# sheet.net
KiCad netlist of a schematic drawn in Altium Designer
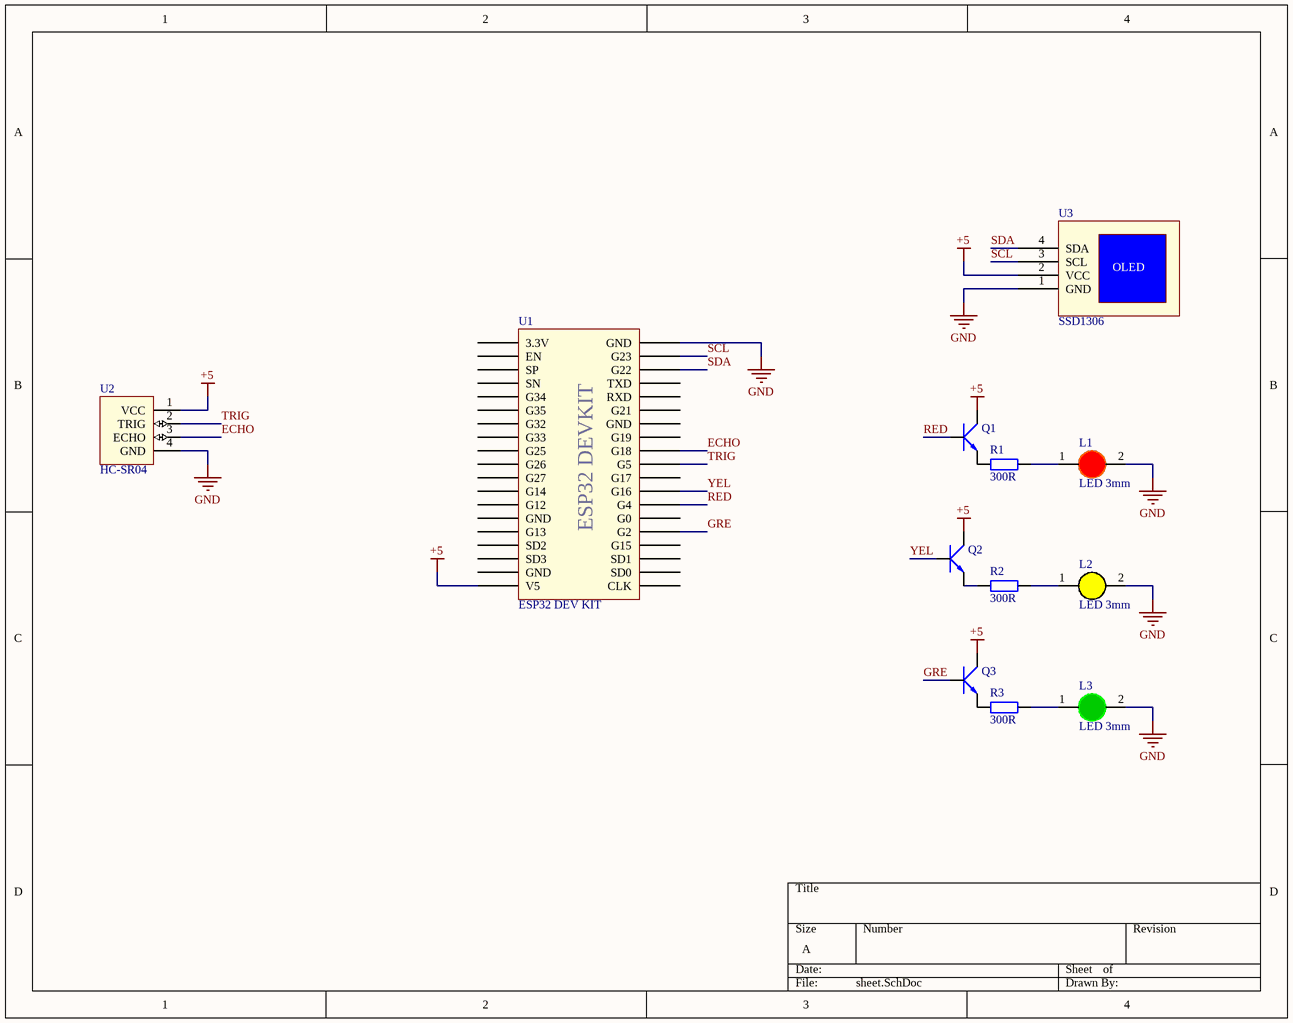
[diagram p0: sheet.SchDoc]

(export (version "E")
  (design (tool "Eeschema 10.0.6"))
  (components
    (comp (ref "L1")
      (value "LED 3mm")
      (footprint "LED-3MM-RED")
      (description "Cắm")
      (libsource (lib "Altium_Lib_by_KhueNguyenCreator") (part "LED 3mm Do"))
    )
    (comp (ref "L2")
      (value "LED 3mm")
      (footprint "LED-3MM-YELLOW")
      (description "Cắm")
      (libsource (lib "Altium_Lib_by_KhueNguyenCreator") (part "LED 3mm Vang"))
    )
    (comp (ref "L3")
      (value "LED 3mm")
      (footprint "LED-3MM-GREEN")
      (description "Cắm")
      (libsource (lib "Altium_Lib_by_KhueNguyenCreator") (part "LED 3mm Xanh La"))
    )
    (comp (ref "Q1")
      (value "?")
      (footprint "TO92")
      (description "NPN transistor EBC")
      (libsource (lib "Altium_Lib_by_KhueNguyenCreator") (part "Trans 2N3904"))
    )
    (comp (ref "Q2")
      (value "?")
      (footprint "TO92")
      (description "NPN transistor EBC")
      (libsource (lib "Altium_Lib_by_KhueNguyenCreator") (part "Trans 2N3904"))
    )
    (comp (ref "Q3")
      (value "?")
      (footprint "TO92")
      (description "NPN transistor EBC")
      (libsource (lib "Altium_Lib_by_KhueNguyenCreator") (part "Trans 2N3904"))
    )
    (comp (ref "R1")
      (value "300R")
      (footprint "tro vach 1/4w")
      (description "Cắm")
      (libsource (lib "Altium_Lib_by_KhueNguyenCreator") (part "Tro Vach 1/4W 5% 300R"))
    )
    (comp (ref "R2")
      (value "300R")
      (footprint "tro vach 1/4w")
      (description "Cắm")
      (libsource (lib "Altium_Lib_by_KhueNguyenCreator") (part "Tro Vach 1/4W 5% 300R"))
    )
    (comp (ref "R3")
      (value "300R")
      (footprint "tro vach 1/4w")
      (description "Cắm")
      (libsource (lib "Altium_Lib_by_KhueNguyenCreator") (part "Tro Vach 1/4W 5% 300R"))
    )
    (comp (ref "U1")
      (value "ESP32 DEV KIT")
      (footprint "ESP32 DEVKIT")
      (libsource (lib "Altium_Lib_by_KhueNguyenCreator") (part "ESP32 DEV KIT"))
    )
    (comp (ref "U2")
      (value "HC-SR04")
      (footprint "HC-SR04_Footprint")
      (libsource (lib "SCHLib") (part "HC-SR04"))
    )
    (comp (ref "U3")
      (value "SSD1306")
      (footprint "OLED-SSD1306_Footprint")
      (libsource (lib "SCHLib") (part "OLED-SSD1306"))
    )
  )
  (nets
    (net (code "1") (name "+5") (class "Default")
      (node (ref "Q1") (pin "3") (pinfunction "C_3") (pintype "passive"))
      (node (ref "Q2") (pin "3") (pinfunction "C_3") (pintype "passive"))
      (node (ref "Q3") (pin "3") (pinfunction "C_3") (pintype "passive"))
      (node (ref "U1") (pin "19") (pinfunction "V5_19") (pintype "passive"))
      (node (ref "U2") (pin "1") (pinfunction "VCC_1") (pintype "power_in"))
      (node (ref "U3") (pin "2") (pinfunction "VCC_2") (pintype "passive"))
    )
    (net (code "2") (name "/ECHO") (class "Default")
      (node (ref "U1") (pin "30") (pinfunction "G18_30") (pintype "passive"))
      (node (ref "U2") (pin "3") (pinfunction "ECHO_3") (pintype "bidirectional"))
    )
    (net (code "3") (name "/GRE") (class "Default")
      (node (ref "Q3") (pin "2") (pinfunction "B_2") (pintype "passive"))
      (node (ref "U1") (pin "24") (pinfunction "G2_24") (pintype "passive"))
    )
    (net (code "4") (name "/RED") (class "Default")
      (node (ref "Q1") (pin "2") (pinfunction "B_2") (pintype "passive"))
      (node (ref "U1") (pin "26") (pinfunction "G4_26") (pintype "passive"))
    )
    (net (code "5") (name "/SCL") (class "Default")
      (node (ref "U1") (pin "37") (pinfunction "G23_37") (pintype "passive"))
      (node (ref "U3") (pin "3") (pinfunction "SCL_3") (pintype "passive"))
    )
    (net (code "6") (name "/SDA") (class "Default")
      (node (ref "U1") (pin "36") (pinfunction "G22_36") (pintype "passive"))
      (node (ref "U3") (pin "4") (pinfunction "SDA_4") (pintype "passive"))
    )
    (net (code "7") (name "/TRIG") (class "Default")
      (node (ref "U1") (pin "29") (pinfunction "G5_29") (pintype "passive"))
      (node (ref "U2") (pin "2") (pinfunction "TRIG_2") (pintype "bidirectional"))
    )
    (net (code "8") (name "/YEL") (class "Default")
      (node (ref "Q2") (pin "2") (pinfunction "B_2") (pintype "passive"))
      (node (ref "U1") (pin "27") (pinfunction "G16_27") (pintype "passive"))
    )
    (net (code "9") (name "GND") (class "Default")
      (node (ref "L1") (pin "2") (pinfunction "K_2") (pintype "passive"))
      (node (ref "L2") (pin "2") (pinfunction "K_2") (pintype "passive"))
      (node (ref "L3") (pin "2") (pinfunction "K_2") (pintype "passive"))
      (node (ref "U1") (pin "38") (pinfunction "GND_38") (pintype "passive"))
      (node (ref "U2") (pin "4") (pinfunction "GND_4") (pintype "power_in"))
      (node (ref "U3") (pin "1") (pinfunction "GND_1") (pintype "passive"))
    )
    (net (code "10") (name "Net-(L1-A)") (class "Default")
      (node (ref "L1") (pin "1") (pinfunction "A_1") (pintype "passive"))
      (node (ref "R1") (pin "2") (pinfunction "2_2") (pintype "passive"))
    )
    (net (code "11") (name "Net-(L2-A)") (class "Default")
      (node (ref "L2") (pin "1") (pinfunction "A_1") (pintype "passive"))
      (node (ref "R2") (pin "2") (pinfunction "2_2") (pintype "passive"))
    )
    (net (code "12") (name "Net-(L3-A)") (class "Default")
      (node (ref "L3") (pin "1") (pinfunction "A_1") (pintype "passive"))
      (node (ref "R3") (pin "2") (pinfunction "2_2") (pintype "passive"))
    )
    (net (code "13") (name "Net-(Q1-E)") (class "Default")
      (node (ref "Q1") (pin "1") (pinfunction "E_1") (pintype "passive"))
      (node (ref "R1") (pin "1") (pinfunction "1_1") (pintype "passive"))
    )
    (net (code "14") (name "Net-(Q2-E)") (class "Default")
      (node (ref "Q2") (pin "1") (pinfunction "E_1") (pintype "passive"))
      (node (ref "R2") (pin "1") (pinfunction "1_1") (pintype "passive"))
    )
    (net (code "15") (name "Net-(Q3-E)") (class "Default")
      (node (ref "Q3") (pin "1") (pinfunction "E_1") (pintype "passive"))
      (node (ref "R3") (pin "1") (pinfunction "1_1") (pintype "passive"))
    )
    (net (code "16") (name "unconnected-(U1-3.3V-Pad1)") (class "Default")
      (node (ref "U1") (pin "1") (pinfunction "3.3V_1") (pintype "passive"))
    )
    (net (code "17") (name "unconnected-(U1-CLK-Pad20)") (class "Default")
      (node (ref "U1") (pin "20") (pinfunction "CLK_20") (pintype "passive"))
    )
    (net (code "18") (name "unconnected-(U1-EN-Pad2)") (class "Default")
      (node (ref "U1") (pin "2") (pinfunction "EN_2") (pintype "passive"))
    )
    (net (code "19") (name "unconnected-(U1-G0-Pad25)") (class "Default")
      (node (ref "U1") (pin "25") (pinfunction "G0_25") (pintype "passive"))
    )
    (net (code "20") (name "unconnected-(U1-G12-Pad13)") (class "Default")
      (node (ref "U1") (pin "13") (pinfunction "G12_13") (pintype "passive"))
    )
    (net (code "21") (name "unconnected-(U1-G13-Pad15)") (class "Default")
      (node (ref "U1") (pin "15") (pinfunction "G13_15") (pintype "passive"))
    )
    (net (code "22") (name "unconnected-(U1-G14-Pad12)") (class "Default")
      (node (ref "U1") (pin "12") (pinfunction "G14_12") (pintype "passive"))
    )
    (net (code "23") (name "unconnected-(U1-G15-Pad23)") (class "Default")
      (node (ref "U1") (pin "23") (pinfunction "G15_23") (pintype "passive"))
    )
    (net (code "24") (name "unconnected-(U1-G17-Pad28)") (class "Default")
      (node (ref "U1") (pin "28") (pinfunction "G17_28") (pintype "passive"))
    )
    (net (code "25") (name "unconnected-(U1-G19-Pad31)") (class "Default")
      (node (ref "U1") (pin "31") (pinfunction "G19_31") (pintype "passive"))
    )
    (net (code "26") (name "unconnected-(U1-G21-Pad33)") (class "Default")
      (node (ref "U1") (pin "33") (pinfunction "G21_33") (pintype "passive"))
    )
    (net (code "27") (name "unconnected-(U1-G25-Pad9)") (class "Default")
      (node (ref "U1") (pin "9") (pinfunction "G25_9") (pintype "passive"))
    )
    (net (code "28") (name "unconnected-(U1-G26-Pad10)") (class "Default")
      (node (ref "U1") (pin "10") (pinfunction "G26_10") (pintype "passive"))
    )
    (net (code "29") (name "unconnected-(U1-G27-Pad11)") (class "Default")
      (node (ref "U1") (pin "11") (pinfunction "G27_11") (pintype "passive"))
    )
    (net (code "30") (name "unconnected-(U1-G32-Pad7)") (class "Default")
      (node (ref "U1") (pin "7") (pinfunction "G32_7") (pintype "passive"))
    )
    (net (code "31") (name "unconnected-(U1-G33-Pad8)") (class "Default")
      (node (ref "U1") (pin "8") (pinfunction "G33_8") (pintype "passive"))
    )
    (net (code "32") (name "unconnected-(U1-G34-Pad5)") (class "Default")
      (node (ref "U1") (pin "5") (pinfunction "G34_5") (pintype "passive"))
    )
    (net (code "33") (name "unconnected-(U1-G35-Pad6)") (class "Default")
      (node (ref "U1") (pin "6") (pinfunction "G35_6") (pintype "passive"))
    )
    (net (code "34") (name "unconnected-(U1-GND-Pad14)") (class "Default")
      (node (ref "U1") (pin "14") (pinfunction "GND_14") (pintype "passive"))
    )
    (net (code "35") (name "unconnected-(U1-GND-Pad18)") (class "Default")
      (node (ref "U1") (pin "18") (pinfunction "GND_18") (pintype "passive"))
    )
    (net (code "36") (name "unconnected-(U1-GND-Pad32)") (class "Default")
      (node (ref "U1") (pin "32") (pinfunction "GND_32") (pintype "passive"))
    )
    (net (code "37") (name "unconnected-(U1-RXD-Pad34)") (class "Default")
      (node (ref "U1") (pin "34") (pinfunction "RXD_34") (pintype "passive"))
    )
    (net (code "38") (name "unconnected-(U1-SD0-Pad21)") (class "Default")
      (node (ref "U1") (pin "21") (pinfunction "SD0_21") (pintype "passive"))
    )
    (net (code "39") (name "unconnected-(U1-SD1-Pad22)") (class "Default")
      (node (ref "U1") (pin "22") (pinfunction "SD1_22") (pintype "passive"))
    )
    (net (code "40") (name "unconnected-(U1-SD2-Pad16)") (class "Default")
      (node (ref "U1") (pin "16") (pinfunction "SD2_16") (pintype "passive"))
    )
    (net (code "41") (name "unconnected-(U1-SD3-Pad17)") (class "Default")
      (node (ref "U1") (pin "17") (pinfunction "SD3_17") (pintype "passive"))
    )
    (net (code "42") (name "unconnected-(U1-SN-Pad4)") (class "Default")
      (node (ref "U1") (pin "4") (pinfunction "SN_4") (pintype "passive"))
    )
    (net (code "43") (name "unconnected-(U1-SP-Pad3)") (class "Default")
      (node (ref "U1") (pin "3") (pinfunction "SP_3") (pintype "passive"))
    )
    (net (code "44") (name "unconnected-(U1-TXD-Pad35)") (class "Default")
      (node (ref "U1") (pin "35") (pinfunction "TXD_35") (pintype "passive"))
    )
  )
)
